# USB.net
KiCad netlist of a schematic drawn in Altium Designer
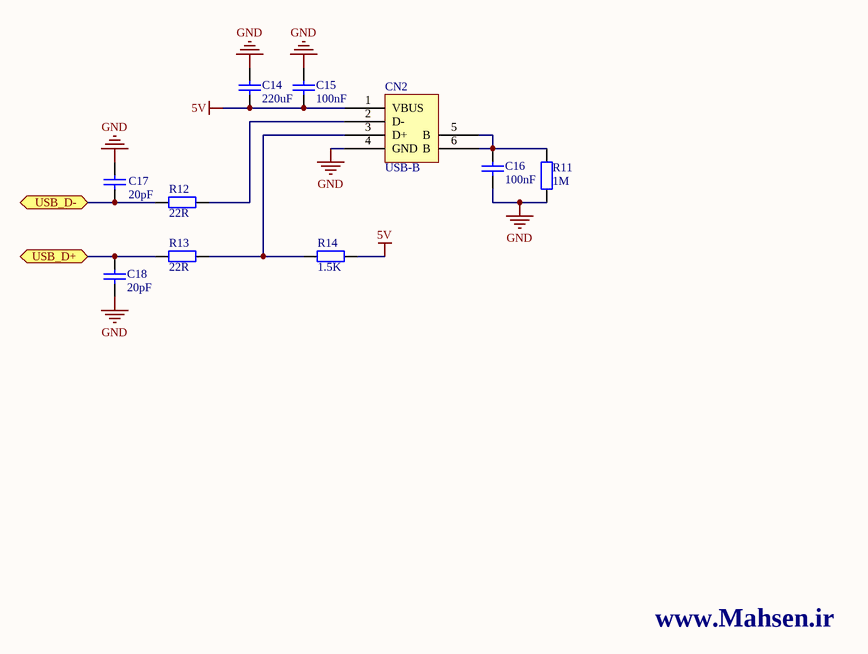
[diagram p0: USB.SchDoc]

(export (version "E")
  (design (tool "Eeschema 10.0.6"))
  (components
    (comp (ref "C14")
      (value "220uF")
      (footprint "0805")
      (description "Capacitor")
      (fields (field (name "PUBLISHER") "Altium Limited"))
      (libsource (lib "Miscellaneous Devices") (part "Cap"))
    )
    (comp (ref "C15")
      (value "100nF")
      (footprint "0805")
      (description "Capacitor")
      (fields (field (name "PUBLISHER") "Altium Limited"))
      (libsource (lib "Miscellaneous Devices") (part "Cap"))
    )
    (comp (ref "C16")
      (value "100nF")
      (footprint "0805")
      (description "Capacitor")
      (fields (field (name "PUBLISHER") "Altium Limited"))
      (libsource (lib "Miscellaneous Devices") (part "Cap"))
    )
    (comp (ref "C17")
      (value "20pF")
      (footprint "0805")
      (description "Capacitor")
      (fields (field (name "PUBLISHER") "Altium Limited"))
      (libsource (lib "Miscellaneous Devices") (part "Cap"))
    )
    (comp (ref "C18")
      (value "20pF")
      (footprint "0805")
      (description "Capacitor")
      (fields (field (name "PUBLISHER") "Altium Limited"))
      (libsource (lib "Miscellaneous Devices") (part "Cap"))
    )
    (comp (ref "CN2") (value "USB-B") (footprint "CONN_USB") (libsource (lib "Lotfi") (part "USB-B")))
    (comp (ref "R11")
      (value "1M")
      (footprint "0805")
      (description "Resistor")
      (fields (field (name "PUBLISHER") "Altium Limited"))
      (libsource (lib "") (part "Res2_1"))
    )
    (comp (ref "R12")
      (value "22R")
      (footprint "0805")
      (description "Resistor")
      (fields (field (name "PUBLISHER") "Altium Limited"))
      (libsource (lib "Miscellaneous Devices") (part "Res2"))
    )
    (comp (ref "R13")
      (value "22R")
      (footprint "0805")
      (description "Resistor")
      (fields (field (name "PUBLISHER") "Altium Limited"))
      (libsource (lib "Miscellaneous Devices") (part "Res2"))
    )
    (comp (ref "R14")
      (value "1.5K")
      (footprint "0805")
      (description "Resistor")
      (fields (field (name "PUBLISHER") "Altium Limited"))
      (libsource (lib "") (part "Res2_2"))
    )
  )
  (nets
    (net (code "1") (name "/USB_D+") (class "Default")
      (node (ref "C18") (pin "1") (pinfunction "1_1") (pintype "passive"))
      (node (ref "R13") (pin "2") (pinfunction "2_2") (pintype "passive"))
    )
    (net (code "2") (name "/USB_D-") (class "Default")
      (node (ref "C17") (pin "2") (pinfunction "2_2") (pintype "passive"))
      (node (ref "R12") (pin "2") (pinfunction "2_2") (pintype "passive"))
    )
    (net (code "3") (name "5V") (class "Default")
      (node (ref "C14") (pin "2") (pinfunction "2_2") (pintype "passive"))
      (node (ref "C15") (pin "2") (pinfunction "2_2") (pintype "passive"))
      (node (ref "CN2") (pin "1") (pinfunction "VBUS_1") (pintype "passive"))
      (node (ref "R14") (pin "2") (pinfunction "2_2") (pintype "passive"))
    )
    (net (code "4") (name "GND") (class "Default")
      (node (ref "C14") (pin "1") (pinfunction "1_1") (pintype "passive"))
      (node (ref "C15") (pin "1") (pinfunction "1_1") (pintype "passive"))
      (node (ref "C16") (pin "2") (pinfunction "2_2") (pintype "passive"))
      (node (ref "C17") (pin "1") (pinfunction "1_1") (pintype "passive"))
      (node (ref "C18") (pin "2") (pinfunction "2_2") (pintype "passive"))
      (node (ref "CN2") (pin "4") (pinfunction "GND_4") (pintype "passive"))
      (node (ref "R11") (pin "1") (pinfunction "1_1") (pintype "passive"))
    )
    (net (code "5") (name "Net-(C16-Pad1)") (class "Default")
      (node (ref "C16") (pin "1") (pinfunction "1_1") (pintype "passive"))
      (node (ref "CN2") (pin "5") (pinfunction "B_5") (pintype "passive"))
      (node (ref "CN2") (pin "6") (pinfunction "B_6") (pintype "passive"))
      (node (ref "R11") (pin "2") (pinfunction "2_2") (pintype "passive"))
    )
    (net (code "6") (name "Net-(CN2-D+)") (class "Default")
      (node (ref "CN2") (pin "3") (pinfunction "D+_3") (pintype "passive"))
      (node (ref "R13") (pin "1") (pinfunction "1_1") (pintype "passive"))
      (node (ref "R14") (pin "1") (pinfunction "1_1") (pintype "passive"))
    )
    (net (code "7") (name "Net-(CN2-D-)") (class "Default")
      (node (ref "CN2") (pin "2") (pinfunction "D-_2") (pintype "passive"))
      (node (ref "R12") (pin "1") (pinfunction "1_1") (pintype "passive"))
    )
  )
)
